# working.net
KiCad netlist of a schematic drawn in EAGLE
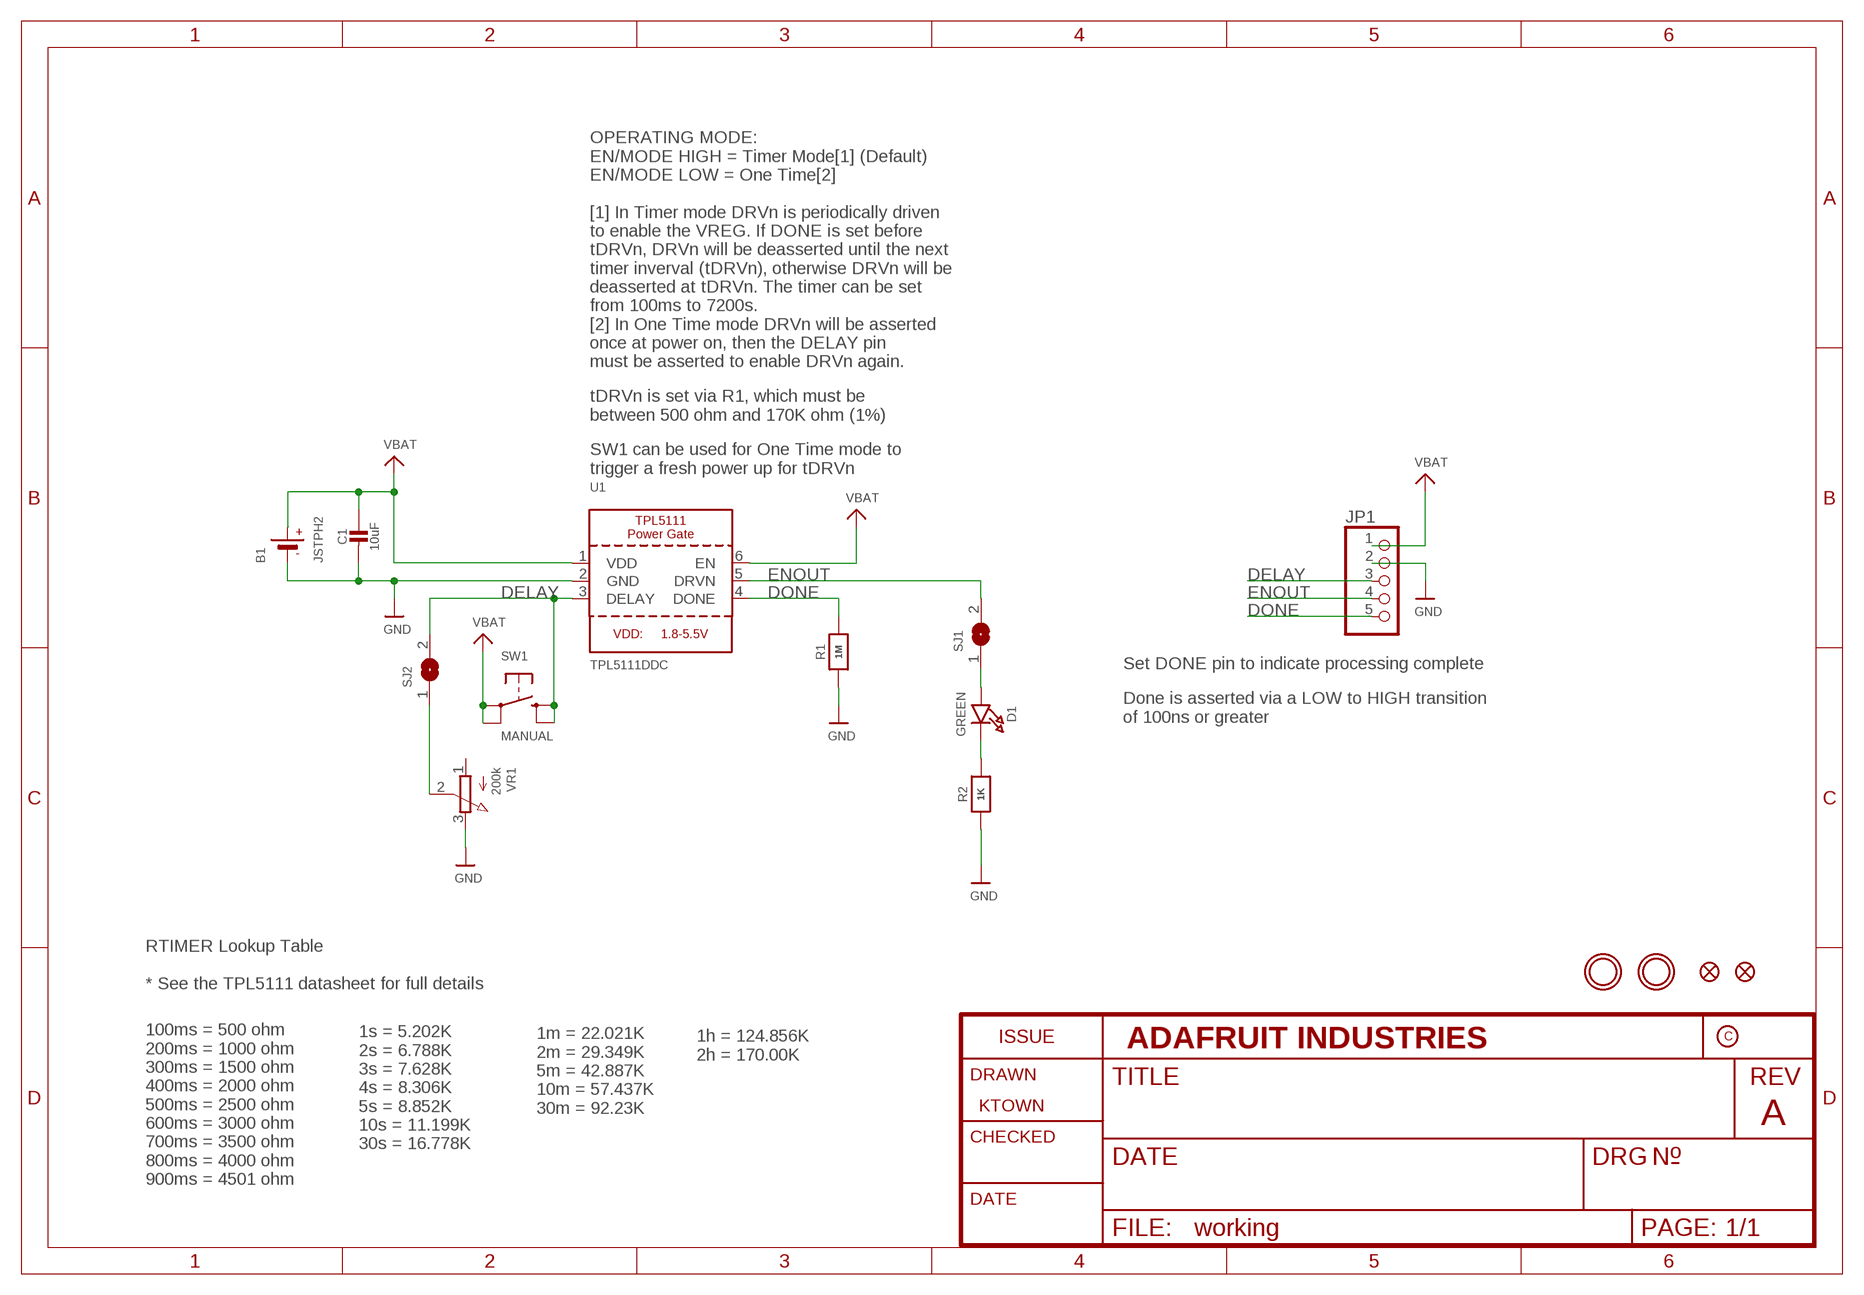
[diagram p0: schematic, sheet 1]

(export (version "E")
  (design (tool "Eeschema 10.0.6"))
  (components
    (comp (ref "B1")
      (value "JSTPH2")
      (footprint "eagle-import:JSTPH2")
      (libsource (lib "eagle-import") (part "BATTERY"))
    )
    (comp (ref "C1")
      (value "10uF")
      (footprint "eagle-import:0805-NO")
      (libsource (lib "eagle-import") (part "CAP_CERAMIC0805-NOOUTLINE"))
    )
    (comp (ref "D1")
      (value "GREEN")
      (footprint "eagle-import:CHIPLED_0805_NOOUTLINE")
      (libsource (lib "eagle-import") (part "LED0805_NOOUTLINE"))
    )
    (comp (ref "FID2")
      (value "FIDUCIAL_1MM")
      (footprint "eagle-import:FIDUCIAL_1MM")
      (libsource (lib "eagle-import") (part "FIDUCIAL_1MM"))
    )
    (comp (ref "FID3")
      (value "FIDUCIAL_1MM")
      (footprint "eagle-import:FIDUCIAL_1MM")
      (libsource (lib "eagle-import") (part "FIDUCIAL_1MM"))
    )
    (comp (ref "JP1")
      (value "HEADER-1X576MIL")
      (footprint "eagle-import:1X05_ROUND_76")
      (libsource (lib "eagle-import") (part "HEADER-1X576MIL"))
    )
    (comp (ref "R1")
      (value "1M")
      (footprint "eagle-import:0805-NO")
      (libsource (lib "eagle-import") (part "RESISTOR0805_NOOUTLINE"))
    )
    (comp (ref "R2")
      (value "1K")
      (footprint "eagle-import:0805-NO")
      (libsource (lib "eagle-import") (part "RESISTOR0805_NOOUTLINE"))
    )
    (comp (ref "SJ1")
      (value "SOLDERJUMPERCLOSED")
      (footprint "eagle-import:SOLDERJUMPER_CLOSEDWIRE")
      (libsource (lib "eagle-import") (part "SOLDERJUMPERCLOSED"))
    )
    (comp (ref "SJ2")
      (value "SOLDERJUMPERCLOSED")
      (footprint "eagle-import:SOLDERJUMPER_CLOSEDWIRE")
      (libsource (lib "eagle-import") (part "SOLDERJUMPERCLOSED"))
    )
    (comp (ref "SW1")
      (value "MANUAL")
      (footprint "eagle-import:EVQ-Q2_SMALLER")
      (libsource (lib "eagle-import") (part "SWITCH_TACT_SMT_EVQQ2_SMALL"))
    )
    (comp (ref "U$8")
      (value "MOUNTINGHOLE2.5")
      (footprint "eagle-import:MOUNTINGHOLE_2.5_PLATED")
      (libsource (lib "eagle-import") (part "MOUNTINGHOLE2.5"))
    )
    (comp (ref "U$9")
      (value "MOUNTINGHOLE2.5")
      (footprint "eagle-import:MOUNTINGHOLE_2.5_PLATED")
      (libsource (lib "eagle-import") (part "MOUNTINGHOLE2.5"))
    )
    (comp (ref "U1")
      (value "TPL5111DDC")
      (footprint "eagle-import:SOT23-6")
      (libsource (lib "eagle-import") (part "TPL5111"))
    )
    (comp (ref "VR1")
      (value "200k")
      (footprint "eagle-import:TRIMPOT_BOURNS_TC33X-2")
      (libsource (lib "eagle-import") (part "TRIMPOTTC33X-2"))
    )
  )
  (nets
    (net (code "1") (name "/DELAY") (class "Default")
      (node (ref "JP1") (pin "3") (pinfunction "3_3") (pintype "passive"))
      (node (ref "SJ2") (pin "2") (pinfunction "2_2") (pintype "passive"))
      (node (ref "SW1") (pin "B") (pinfunction "S_B") (pintype "passive"))
      (node (ref "SW1") (pin "B'") (pinfunction "S1_B'") (pintype "passive"))
      (node (ref "U1") (pin "3") (pinfunction "DELAY_3") (pintype "input"))
    )
    (net (code "2") (name "/DONE") (class "Default")
      (node (ref "JP1") (pin "5") (pinfunction "5_5") (pintype "passive"))
      (node (ref "R1") (pin "2") (pinfunction "2_2") (pintype "passive"))
      (node (ref "U1") (pin "4") (pinfunction "DONE_4") (pintype "input"))
    )
    (net (code "3") (name "/ENOUT") (class "Default")
      (node (ref "JP1") (pin "4") (pinfunction "4_4") (pintype "passive"))
      (node (ref "SJ1") (pin "2") (pinfunction "2_2") (pintype "passive"))
      (node (ref "U1") (pin "5") (pinfunction "DRVN_5") (pintype "output"))
    )
    (net (code "4") (name "GND") (class "Default")
      (node (ref "B1") (pin "1") (pinfunction "-_1") (pintype "passive"))
      (node (ref "C1") (pin "2") (pinfunction "2_2") (pintype "passive"))
      (node (ref "JP1") (pin "2") (pinfunction "2_2") (pintype "passive"))
      (node (ref "R1") (pin "1") (pinfunction "1_1") (pintype "passive"))
      (node (ref "R2") (pin "1") (pinfunction "1_1") (pintype "passive"))
      (node (ref "U1") (pin "2") (pinfunction "GND_2") (pintype "power_in"))
      (node (ref "VR1") (pin "3") (pinfunction "E_3") (pintype "passive"))
    )
    (net (code "5") (name "Net-(D1-PadA)") (class "Default")
      (node (ref "D1") (pin "A") (pinfunction "A_A") (pintype "passive"))
      (node (ref "SJ1") (pin "1") (pinfunction "1_1") (pintype "passive"))
    )
    (net (code "6") (name "Net-(D1-PadC)") (class "Default")
      (node (ref "D1") (pin "C") (pinfunction "C_C") (pintype "passive"))
      (node (ref "R2") (pin "2") (pinfunction "2_2") (pintype "passive"))
    )
    (net (code "7") (name "Net-(VR1-S)") (class "Default")
      (node (ref "SJ2") (pin "1") (pinfunction "1_1") (pintype "passive"))
      (node (ref "VR1") (pin "2") (pinfunction "S_2") (pintype "passive"))
    )
    (net (code "8") (name "VBAT") (class "Default")
      (node (ref "B1") (pin "2") (pinfunction "+_2") (pintype "passive"))
      (node (ref "C1") (pin "1") (pinfunction "1_1") (pintype "passive"))
      (node (ref "JP1") (pin "1") (pinfunction "1_1") (pintype "passive"))
      (node (ref "SW1") (pin "A") (pinfunction "P_A") (pintype "passive"))
      (node (ref "SW1") (pin "A'") (pinfunction "P1_A'") (pintype "passive"))
      (node (ref "U1") (pin "1") (pinfunction "VDD_1") (pintype "power_in"))
      (node (ref "U1") (pin "6") (pinfunction "EN_6") (pintype "input"))
    )
    (net (code "9") (name "unconnected-(VR1-A-Pad1)") (class "Default")
      (node (ref "VR1") (pin "1") (pinfunction "A_1") (pintype "passive"))
    )
  )
)
